# RC_Transmitter_Mini.net
KiCad netlist of a schematic drawn in EasyEDA Pro
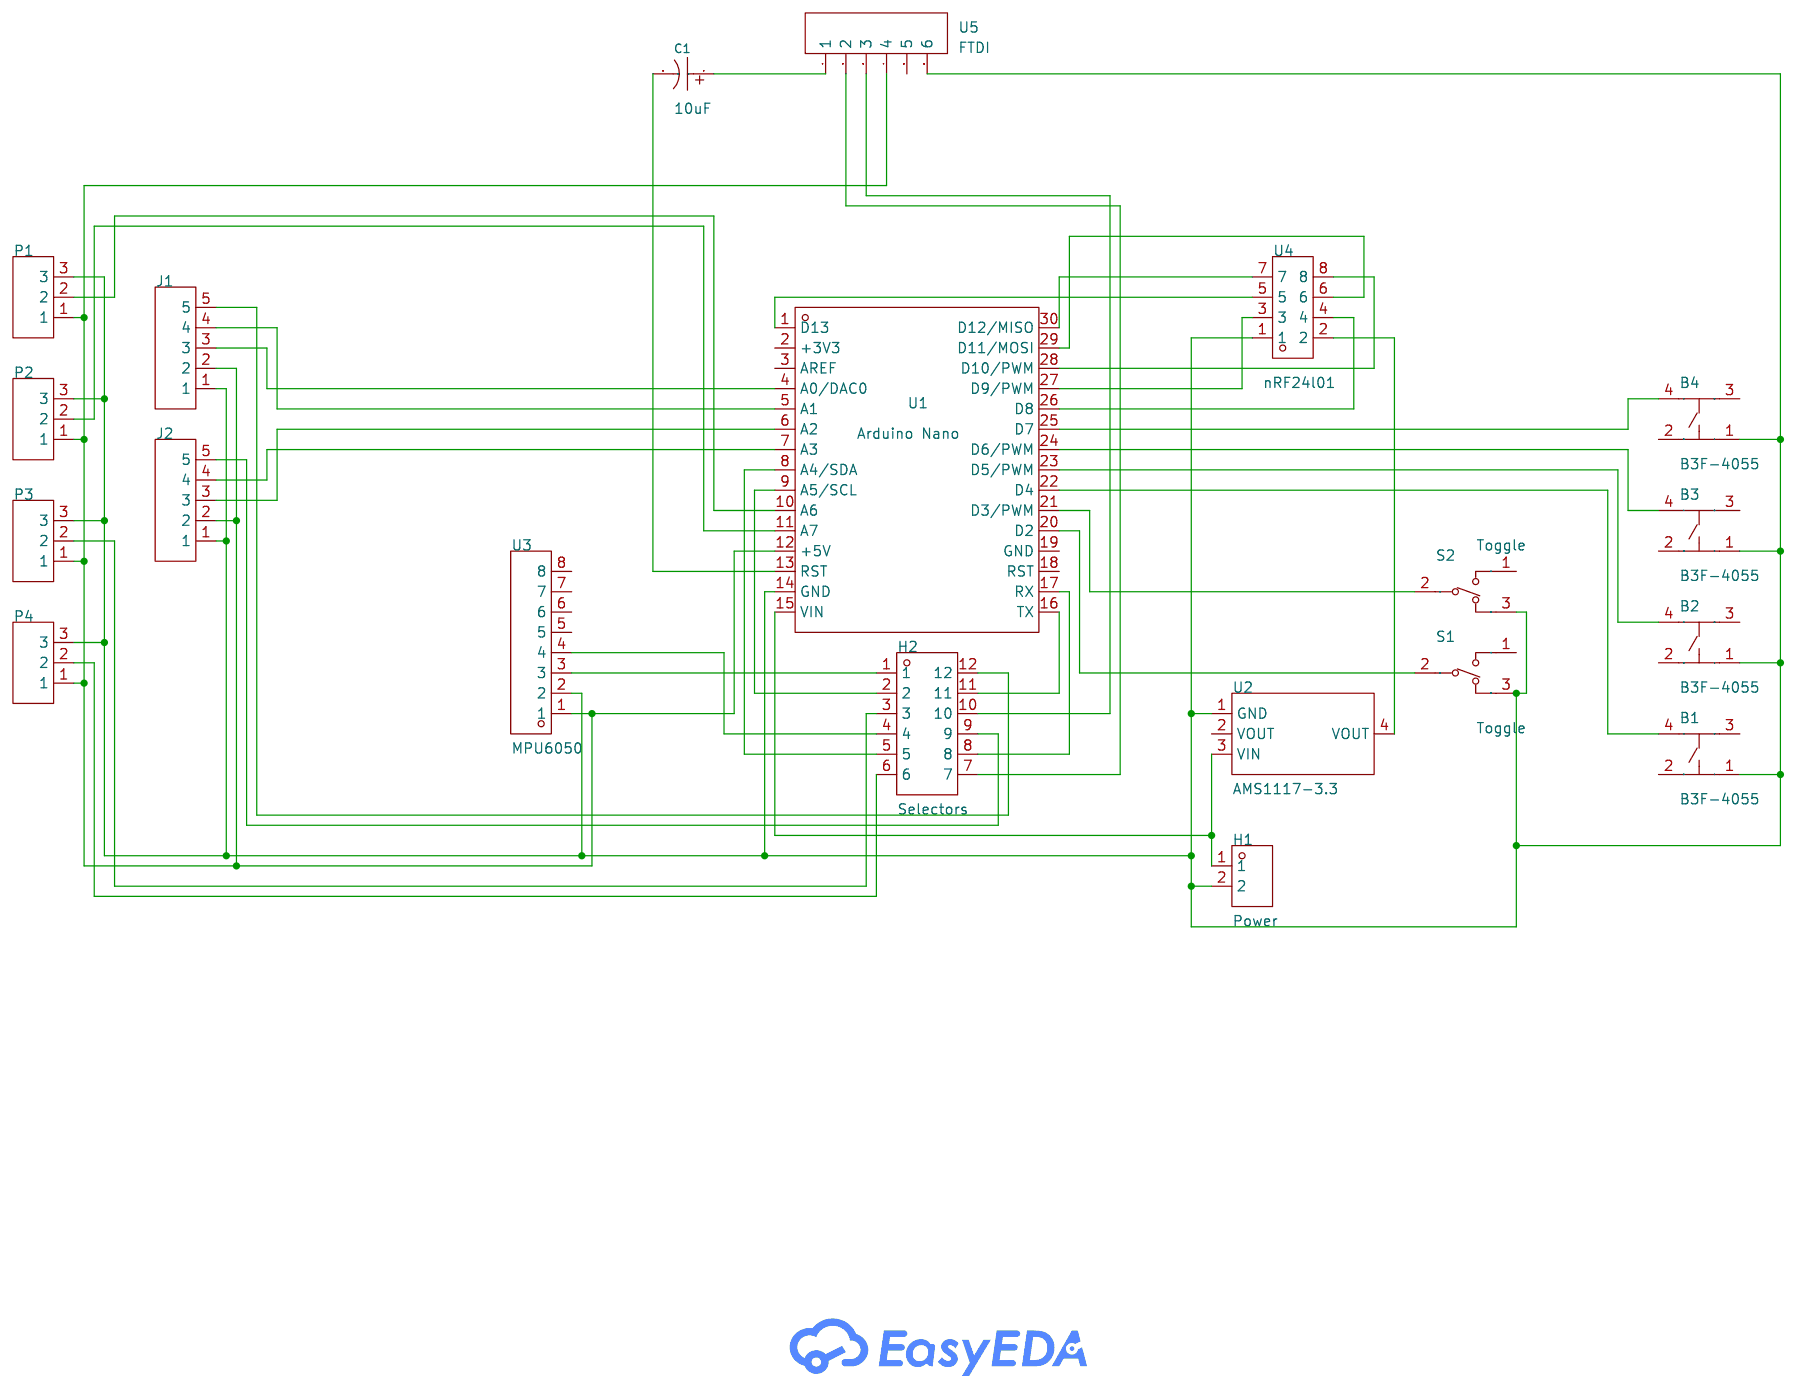
[diagram p0: schematic sheet]

(export (version "E")
  (design (tool "Eeschema 10.0.6"))
  (components
    (comp (ref "B1")
      (value "B3F-4055")
      (footprint "easyedapro:KEY-TH_4P-L12.0-W12.0-P5.00-LS13.4-EH")
      (fields (field (name "Manufacturer") "OMRON(欧姆龙)"))
      (libsource (lib "easyedapro") (part "B3F-4055"))
    )
    (comp (ref "B2")
      (value "B3F-4055")
      (footprint "easyedapro:KEY-TH_4P-L12.0-W12.0-P5.00-LS13.4-EH")
      (fields (field (name "Manufacturer") "OMRON(欧姆龙)"))
      (libsource (lib "easyedapro") (part "B3F-4055"))
    )
    (comp (ref "B3")
      (value "B3F-4055")
      (footprint "easyedapro:KEY-TH_4P-L12.0-W12.0-P5.00-LS13.4-EH")
      (fields (field (name "Manufacturer") "OMRON(欧姆龙)"))
      (libsource (lib "easyedapro") (part "B3F-4055"))
    )
    (comp (ref "B4")
      (value "B3F-4055")
      (footprint "easyedapro:KEY-TH_4P-L12.0-W12.0-P5.00-LS13.4-EH")
      (fields (field (name "Manufacturer") "OMRON(欧姆龙)"))
      (libsource (lib "easyedapro") (part "B3F-4055"))
    )
    (comp (ref "C1")
      (value "10uF")
      (footprint "easyedapro:CAP-TH_BD5.0-P2.00-D0.8-FD")
      (fields (field (name "Manufacturer Part") "RD1H106M05011PC") (field (name "Manufacturer") "SAMWHA(三和)"))
      (libsource (lib "easyedapro") (part "RD1H106M05011PC"))
    )
    (comp (ref "H1")
      (value "Power")
      (footprint "easyedapro:HDR-TH_2P-P2.54-V-M_5")
      (fields (field (name "Manufacturer") "HCTL(华灿天禄)"))
      (libsource (lib "easyedapro") (part "PZ254-1-02-Z-C"))
    )
    (comp (ref "H2")
      (value "Selectors")
      (footprint "easyedapro:HDR-TH_12P-P2.54-V-M-R3-C4-S2.54")
      (fields (field (name "Manufacturer") "hanxia(韩下)"))
      (libsource (lib "easyedapro") (part "HX PZ2.54-3X4P ZZ"))
    )
    (comp (ref "J1")
      (value "HB-PH3-25415PB2GOP")
      (footprint "easyedapro:HDR-TH_5P-P2.54-V-M")
      (fields (field (name "Manufacturer") "HANBO(汉博)"))
      (libsource (lib "easyedapro") (part "HB-PH3-25415PB2GOP"))
    )
    (comp (ref "J2")
      (value "HB-PH3-25415PB2GOP")
      (footprint "easyedapro:HDR-TH_5P-P2.54-V-M")
      (fields (field (name "Manufacturer") "HANBO(汉博)"))
      (libsource (lib "easyedapro") (part "HB-PH3-25415PB2GOP"))
    )
    (comp (ref "P1")
      (value "PZ254V-11-03P")
      (footprint "easyedapro:HDR-TH_3P-P2.54-V-M")
      (fields (field (name "Manufacturer") "XFCN(兴飞)"))
      (libsource (lib "easyedapro") (part "PZ254V-11-03P_C2937625"))
    )
    (comp (ref "P2")
      (value "PZ254V-11-03P")
      (footprint "easyedapro:HDR-TH_3P-P2.54-V-M")
      (fields (field (name "Manufacturer") "XFCN(兴飞)"))
      (libsource (lib "easyedapro") (part "PZ254V-11-03P_C2937625"))
    )
    (comp (ref "P3")
      (value "PZ254V-11-03P")
      (footprint "easyedapro:HDR-TH_3P-P2.54-V-M")
      (fields (field (name "Manufacturer") "XFCN(兴飞)"))
      (libsource (lib "easyedapro") (part "PZ254V-11-03P_C2937625"))
    )
    (comp (ref "P4")
      (value "PZ254V-11-03P")
      (footprint "easyedapro:HDR-TH_3P-P2.54-V-M")
      (fields (field (name "Manufacturer") "XFCN(兴飞)"))
      (libsource (lib "easyedapro") (part "PZ254V-11-03P_C2937625"))
    )
    (comp (ref "S1")
      (value "Toggle")
      (footprint "easyedapro:SW-TH_ST-0-103-A01")
      (fields (field (name "Manufacturer") "YUEN FUNG(源丰)"))
      (libsource (lib "easyedapro") (part "ST-0-103-A01-T000-RS"))
    )
    (comp (ref "S2")
      (value "Toggle")
      (footprint "easyedapro:SW-TH_ST-0-103-A01")
      (fields (field (name "Manufacturer") "YUEN FUNG(源丰)"))
      (libsource (lib "easyedapro") (part "ST-0-103-A01-T000-RS"))
    )
    (comp (ref "U1")
      (value "Arduino Nano")
      (footprint "easyedapro:MOD-TH_ABX00028")
      (fields (field (name "Manufacturer") "arduino"))
      (libsource (lib "easyedapro") (part "ABX00028"))
    )
    (comp (ref "U2")
      (value "AMS1117-3.3")
      (footprint "easyedapro:SOT-223-3_L6.5-W3.4-P2.30-LS7.0-BR")
      (fields (field (name "Manufacturer") "AMS"))
      (libsource (lib "easyedapro") (part "AMS1117-3.3"))
    )
    (comp (ref "U3")
      (value "MPU6050")
      (footprint "easyedapro:HDR-TH_8P-P2.54-V-F")
      (fields (field (name "Manufacturer") "kinghelm(金航标)"))
      (libsource (lib "easyedapro") (part "KH-2.54FH-1X8P-H8.5"))
    )
    (comp (ref "U4")
      (value "nRF24l01")
      (footprint "easyedapro:HDR-TH_8P-P2.54-V-F-R2-C4-S2.54")
      (fields (field (name "Manufacturer") "ZHOURI(洲日)"))
      (libsource (lib "easyedapro") (part "2.54-2*4"))
    )
    (comp (ref "U5")
      (value "FTDI")
      (footprint "easyedapro:HDR-TH_6P-P2.54-V-M-1")
      (fields (field (name "Manufacturer") "BOOMELE(博穆精密)"))
      (libsource (lib "easyedapro") (part "Header-Male-2.54_1x6"))
    )
  )
  (nets
    (net (code "1") (name "Net-(C1-Pad1)") (class "Default")
      (node (ref "C1") (pin "1") (pinfunction "1_1") (pintype "input"))
      (node (ref "U5") (pin "1") (pinfunction "1_1") (pintype "input"))
    )
    (net (code "2") (name "Net-(C1-Pad2)") (class "Default")
      (node (ref "C1") (pin "2") (pinfunction "2_2") (pintype "input"))
      (node (ref "U1") (pin "13") (pinfunction "RST_13") (pintype "unspecified"))
    )
    (net (code "3") (name "Net-(H2-Pad1)") (class "Default")
      (node (ref "H2") (pin "1") (pinfunction "1_1") (pintype "unspecified"))
      (node (ref "U3") (pin "3") (pinfunction "3_3") (pintype "unspecified"))
    )
    (net (code "4") (name "Net-(H2-Pad3)") (class "Default")
      (node (ref "H2") (pin "3") (pinfunction "3_3") (pintype "unspecified"))
      (node (ref "P3") (pin "2") (pinfunction "2_2") (pintype "unspecified"))
    )
    (net (code "5") (name "Net-(H2-Pad4)") (class "Default")
      (node (ref "H2") (pin "4") (pinfunction "4_4") (pintype "unspecified"))
      (node (ref "U3") (pin "4") (pinfunction "4_4") (pintype "unspecified"))
    )
    (net (code "6") (name "Net-(H2-Pad6)") (class "Default")
      (node (ref "H2") (pin "6") (pinfunction "6_6") (pintype "unspecified"))
      (node (ref "P4") (pin "2") (pinfunction "2_2") (pintype "unspecified"))
    )
    (net (code "7") (name "Net-(H2-Pad7)") (class "Default")
      (node (ref "H2") (pin "7") (pinfunction "7_7") (pintype "unspecified"))
      (node (ref "U5") (pin "2") (pinfunction "2_2") (pintype "input"))
    )
    (net (code "8") (name "Net-(H2-Pad9)") (class "Default")
      (node (ref "H2") (pin "9") (pinfunction "9_9") (pintype "unspecified"))
      (node (ref "J2") (pin "5") (pinfunction "5_5") (pintype "unspecified"))
    )
    (net (code "9") (name "Net-(H2-Pad10)") (class "Default")
      (node (ref "H2") (pin "10") (pinfunction "10_10") (pintype "unspecified"))
      (node (ref "U5") (pin "3") (pinfunction "3_3") (pintype "input"))
    )
    (net (code "10") (name "Net-(H2-Pad12)") (class "Default")
      (node (ref "H2") (pin "12") (pinfunction "12_12") (pintype "unspecified"))
      (node (ref "J1") (pin "5") (pinfunction "5_5") (pintype "unspecified"))
    )
    (net (code "11") (name "Net-(U1-+5V)") (class "Default")
      (node (ref "J1") (pin "2") (pinfunction "2_2") (pintype "unspecified"))
      (node (ref "J2") (pin "2") (pinfunction "2_2") (pintype "unspecified"))
      (node (ref "P1") (pin "1") (pinfunction "1_1") (pintype "unspecified"))
      (node (ref "P2") (pin "1") (pinfunction "1_1") (pintype "unspecified"))
      (node (ref "P3") (pin "1") (pinfunction "1_1") (pintype "unspecified"))
      (node (ref "P4") (pin "1") (pinfunction "1_1") (pintype "unspecified"))
      (node (ref "U1") (pin "12") (pinfunction "+5V_12") (pintype "unspecified"))
      (node (ref "U3") (pin "1") (pinfunction "1_1") (pintype "unspecified"))
      (node (ref "U5") (pin "4") (pinfunction "4_4") (pintype "input"))
    )
    (net (code "12") (name "Net-(U1-A0{slash}DAC0)") (class "Default")
      (node (ref "J1") (pin "3") (pinfunction "3_3") (pintype "unspecified"))
      (node (ref "U1") (pin "4") (pinfunction "A0/DAC0_4") (pintype "unspecified"))
    )
    (net (code "13") (name "Net-(U1-A1)") (class "Default")
      (node (ref "J1") (pin "4") (pinfunction "4_4") (pintype "unspecified"))
      (node (ref "U1") (pin "5") (pinfunction "A1_5") (pintype "unspecified"))
    )
    (net (code "14") (name "Net-(U1-A2)") (class "Default")
      (node (ref "J2") (pin "3") (pinfunction "3_3") (pintype "unspecified"))
      (node (ref "U1") (pin "6") (pinfunction "A2_6") (pintype "unspecified"))
    )
    (net (code "15") (name "Net-(U1-A3)") (class "Default")
      (node (ref "J2") (pin "4") (pinfunction "4_4") (pintype "unspecified"))
      (node (ref "U1") (pin "7") (pinfunction "A3_7") (pintype "unspecified"))
    )
    (net (code "16") (name "Net-(U1-A4{slash}SDA)") (class "Default")
      (node (ref "H2") (pin "5") (pinfunction "5_5") (pintype "unspecified"))
      (node (ref "U1") (pin "8") (pinfunction "A4/SDA_8") (pintype "unspecified"))
    )
    (net (code "17") (name "Net-(U1-A5{slash}SCL)") (class "Default")
      (node (ref "H2") (pin "2") (pinfunction "2_2") (pintype "unspecified"))
      (node (ref "U1") (pin "9") (pinfunction "A5/SCL_9") (pintype "unspecified"))
    )
    (net (code "18") (name "Net-(U1-A6)") (class "Default")
      (node (ref "P1") (pin "2") (pinfunction "2_2") (pintype "unspecified"))
      (node (ref "U1") (pin "10") (pinfunction "A6_10") (pintype "unspecified"))
    )
    (net (code "19") (name "Net-(U1-A7)") (class "Default")
      (node (ref "P2") (pin "2") (pinfunction "2_2") (pintype "unspecified"))
      (node (ref "U1") (pin "11") (pinfunction "A7_11") (pintype "unspecified"))
    )
    (net (code "20") (name "Net-(U1-D2)") (class "Default")
      (node (ref "S1") (pin "2") (pinfunction "2_2") (pintype "unspecified"))
      (node (ref "U1") (pin "20") (pinfunction "D2_20") (pintype "unspecified"))
    )
    (net (code "21") (name "Net-(U1-D3{slash}PWM)") (class "Default")
      (node (ref "S2") (pin "2") (pinfunction "2_2") (pintype "unspecified"))
      (node (ref "U1") (pin "21") (pinfunction "D3/PWM_21") (pintype "unspecified"))
    )
    (net (code "22") (name "Net-(U1-D4)") (class "Default")
      (node (ref "B1") (pin "4") (pinfunction "4_4") (pintype "unspecified"))
      (node (ref "U1") (pin "22") (pinfunction "D4_22") (pintype "unspecified"))
    )
    (net (code "23") (name "Net-(U1-D5{slash}PWM)") (class "Default")
      (node (ref "B2") (pin "4") (pinfunction "4_4") (pintype "unspecified"))
      (node (ref "U1") (pin "23") (pinfunction "D5/PWM_23") (pintype "unspecified"))
    )
    (net (code "24") (name "Net-(U1-D6{slash}PWM)") (class "Default")
      (node (ref "B3") (pin "4") (pinfunction "4_4") (pintype "unspecified"))
      (node (ref "U1") (pin "24") (pinfunction "D6/PWM_24") (pintype "unspecified"))
    )
    (net (code "25") (name "Net-(U1-D7)") (class "Default")
      (node (ref "B4") (pin "4") (pinfunction "4_4") (pintype "unspecified"))
      (node (ref "U1") (pin "25") (pinfunction "D7_25") (pintype "unspecified"))
    )
    (net (code "26") (name "Net-(U1-D8)") (class "Default")
      (node (ref "U1") (pin "26") (pinfunction "D8_26") (pintype "unspecified"))
      (node (ref "U4") (pin "4") (pinfunction "4_4") (pintype "unspecified"))
    )
    (net (code "27") (name "Net-(U1-D9{slash}PWM)") (class "Default")
      (node (ref "U1") (pin "27") (pinfunction "D9/PWM_27") (pintype "unspecified"))
      (node (ref "U4") (pin "3") (pinfunction "3_3") (pintype "unspecified"))
    )
    (net (code "28") (name "Net-(U1-D10{slash}PWM)") (class "Default")
      (node (ref "U1") (pin "28") (pinfunction "D10/PWM_28") (pintype "unspecified"))
      (node (ref "U4") (pin "8") (pinfunction "8_8") (pintype "unspecified"))
    )
    (net (code "29") (name "Net-(U1-D11{slash}MOSI)") (class "Default")
      (node (ref "U1") (pin "29") (pinfunction "D11/MOSI_29") (pintype "unspecified"))
      (node (ref "U4") (pin "6") (pinfunction "6_6") (pintype "unspecified"))
    )
    (net (code "30") (name "Net-(U1-D12{slash}MISO)") (class "Default")
      (node (ref "U1") (pin "30") (pinfunction "D12/MISO_30") (pintype "unspecified"))
      (node (ref "U4") (pin "7") (pinfunction "7_7") (pintype "unspecified"))
    )
    (net (code "31") (name "Net-(U1-D13)") (class "Default")
      (node (ref "U1") (pin "1") (pinfunction "D13_1") (pintype "unspecified"))
      (node (ref "U4") (pin "5") (pinfunction "5_5") (pintype "unspecified"))
    )
    (net (code "32") (name "Net-(U1-RX)") (class "Default")
      (node (ref "H2") (pin "8") (pinfunction "8_8") (pintype "unspecified"))
      (node (ref "U1") (pin "17") (pinfunction "RX_17") (pintype "unspecified"))
    )
    (net (code "33") (name "Net-(U1-TX)") (class "Default")
      (node (ref "H2") (pin "11") (pinfunction "11_11") (pintype "unspecified"))
      (node (ref "U1") (pin "16") (pinfunction "TX_16") (pintype "unspecified"))
    )
    (net (code "34") (name "Net-(U1-VIN)") (class "Default")
      (node (ref "H1") (pin "1") (pinfunction "1_1") (pintype "unspecified"))
      (node (ref "U1") (pin "15") (pinfunction "VIN_15") (pintype "unspecified"))
      (node (ref "U2") (pin "3") (pinfunction "VIN_3") (pintype "unspecified"))
    )
    (net (code "35") (name "Net-(U2-GND)") (class "Default")
      (node (ref "B1") (pin "1") (pinfunction "1_1") (pintype "unspecified"))
      (node (ref "B2") (pin "1") (pinfunction "1_1") (pintype "unspecified"))
      (node (ref "B3") (pin "1") (pinfunction "1_1") (pintype "unspecified"))
      (node (ref "B4") (pin "1") (pinfunction "1_1") (pintype "unspecified"))
      (node (ref "H1") (pin "2") (pinfunction "2_2") (pintype "unspecified"))
      (node (ref "J1") (pin "1") (pinfunction "1_1") (pintype "unspecified"))
      (node (ref "J2") (pin "1") (pinfunction "1_1") (pintype "unspecified"))
      (node (ref "P1") (pin "3") (pinfunction "3_3") (pintype "unspecified"))
      (node (ref "P2") (pin "3") (pinfunction "3_3") (pintype "unspecified"))
      (node (ref "P3") (pin "3") (pinfunction "3_3") (pintype "unspecified"))
      (node (ref "P4") (pin "3") (pinfunction "3_3") (pintype "unspecified"))
      (node (ref "S1") (pin "3") (pinfunction "3_3") (pintype "unspecified"))
      (node (ref "S2") (pin "3") (pinfunction "3_3") (pintype "unspecified"))
      (node (ref "U1") (pin "14") (pinfunction "GND_14") (pintype "unspecified"))
      (node (ref "U2") (pin "1") (pinfunction "GND_1") (pintype "unspecified"))
      (node (ref "U3") (pin "2") (pinfunction "2_2") (pintype "unspecified"))
      (node (ref "U4") (pin "1") (pinfunction "1_1") (pintype "unspecified"))
      (node (ref "U5") (pin "6") (pinfunction "6_6") (pintype "input"))
    )
    (net (code "36") (name "Net-(U2-VOUT-Pad4)") (class "Default")
      (node (ref "U2") (pin "4") (pinfunction "VOUT_4") (pintype "unspecified"))
      (node (ref "U4") (pin "2") (pinfunction "2_2") (pintype "unspecified"))
    )
    (net (code "37") (name "unconnected-(B1-Pad2)") (class "Default")
      (node (ref "B1") (pin "2") (pinfunction "2_2") (pintype "unspecified"))
    )
    (net (code "38") (name "unconnected-(B1-Pad3)") (class "Default")
      (node (ref "B1") (pin "3") (pinfunction "3_3") (pintype "unspecified"))
    )
    (net (code "39") (name "unconnected-(B2-Pad2)") (class "Default")
      (node (ref "B2") (pin "2") (pinfunction "2_2") (pintype "unspecified"))
    )
    (net (code "40") (name "unconnected-(B2-Pad3)") (class "Default")
      (node (ref "B2") (pin "3") (pinfunction "3_3") (pintype "unspecified"))
    )
    (net (code "41") (name "unconnected-(B3-Pad2)") (class "Default")
      (node (ref "B3") (pin "2") (pinfunction "2_2") (pintype "unspecified"))
    )
    (net (code "42") (name "unconnected-(B3-Pad3)") (class "Default")
      (node (ref "B3") (pin "3") (pinfunction "3_3") (pintype "unspecified"))
    )
    (net (code "43") (name "unconnected-(B4-Pad2)") (class "Default")
      (node (ref "B4") (pin "2") (pinfunction "2_2") (pintype "unspecified"))
    )
    (net (code "44") (name "unconnected-(B4-Pad3)") (class "Default")
      (node (ref "B4") (pin "3") (pinfunction "3_3") (pintype "unspecified"))
    )
    (net (code "45") (name "unconnected-(S1-Pad1)") (class "Default")
      (node (ref "S1") (pin "1") (pinfunction "1_1") (pintype "unspecified"))
    )
    (net (code "46") (name "unconnected-(S2-Pad1)") (class "Default")
      (node (ref "S2") (pin "1") (pinfunction "1_1") (pintype "unspecified"))
    )
    (net (code "47") (name "unconnected-(U1-+3V3-Pad2)") (class "Default")
      (node (ref "U1") (pin "2") (pinfunction "+3V3_2") (pintype "unspecified"))
    )
    (net (code "48") (name "unconnected-(U1-AREF-Pad3)") (class "Default")
      (node (ref "U1") (pin "3") (pinfunction "AREF_3") (pintype "unspecified"))
    )
    (net (code "49") (name "unconnected-(U1-GND-Pad19)") (class "Default")
      (node (ref "U1") (pin "19") (pinfunction "GND_19") (pintype "unspecified"))
    )
    (net (code "50") (name "unconnected-(U1-RST-Pad18)") (class "Default")
      (node (ref "U1") (pin "18") (pinfunction "RST_18") (pintype "unspecified"))
    )
    (net (code "51") (name "unconnected-(U2-VOUT-Pad2)") (class "Default")
      (node (ref "U2") (pin "2") (pinfunction "VOUT_2") (pintype "unspecified"))
    )
    (net (code "52") (name "unconnected-(U3-Pad5)") (class "Default")
      (node (ref "U3") (pin "5") (pinfunction "5_5") (pintype "unspecified"))
    )
    (net (code "53") (name "unconnected-(U3-Pad6)") (class "Default")
      (node (ref "U3") (pin "6") (pinfunction "6_6") (pintype "unspecified"))
    )
    (net (code "54") (name "unconnected-(U3-Pad7)") (class "Default")
      (node (ref "U3") (pin "7") (pinfunction "7_7") (pintype "unspecified"))
    )
    (net (code "55") (name "unconnected-(U3-Pad8)") (class "Default")
      (node (ref "U3") (pin "8") (pinfunction "8_8") (pintype "unspecified"))
    )
    (net (code "56") (name "unconnected-(U5-Pad5)") (class "Default")
      (node (ref "U5") (pin "5") (pinfunction "5_5") (pintype "input"))
    )
  )
)
